# led-group-thin.net
KiCad netlist of a schematic drawn in Altium Designer
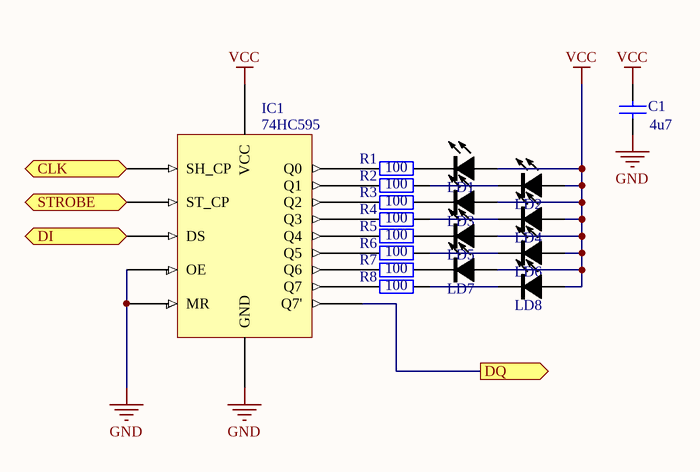
[diagram p0: led-group-thin.SchDoc]

(export (version "E")
  (design (tool "Eeschema 10.0.6"))
  (components
    (comp (ref "C1")
      (value "4u7")
      (footprint "6-0805_M")
      (description "Capacitor")
      (fields (field (name "Comment") "Cap"))
      (libsource (lib "Miscellaneous Devices") (part "Cap"))
    )
    (comp (ref "IC1")
      (value "74HC595")
      (footprint "TSSOP16")
      (description "74HC595 8-bit latched SIPO shift register")
      (libsource (lib "Components") (part "Component_1"))
    )
    (comp (ref "LD1") (value "UV-LED") (footprint "0805-LED") (libsource (lib "Components") (part "UV-LED")))
    (comp (ref "LD2") (value "UV-LED") (footprint "0805-LED") (libsource (lib "Components") (part "UV-LED")))
    (comp (ref "LD3") (value "UV-LED") (footprint "0805-LED") (libsource (lib "Components") (part "UV-LED")))
    (comp (ref "LD4") (value "UV-LED") (footprint "0805-LED") (libsource (lib "Components") (part "UV-LED")))
    (comp (ref "LD5") (value "UV-LED") (footprint "0805-LED") (libsource (lib "Components") (part "UV-LED")))
    (comp (ref "LD6") (value "UV-LED") (footprint "0805-LED") (libsource (lib "Components") (part "UV-LED")))
    (comp (ref "LD7") (value "UV-LED") (footprint "0805-LED") (libsource (lib "Components") (part "UV-LED")))
    (comp (ref "LD8") (value "UV-LED") (footprint "0805-LED") (libsource (lib "Components") (part "UV-LED")))
    (comp (ref "R1")
      (value "100")
      (footprint "6-0805_N")
      (description "Resistor")
      (libsource (lib "Miscellaneous Devices") (part "Res2"))
    )
    (comp (ref "R2")
      (value "100")
      (footprint "6-0805_N")
      (description "Resistor")
      (libsource (lib "Miscellaneous Devices") (part "Res2"))
    )
    (comp (ref "R3")
      (value "100")
      (footprint "6-0805_N")
      (description "Resistor")
      (libsource (lib "Miscellaneous Devices") (part "Res2"))
    )
    (comp (ref "R4")
      (value "100")
      (footprint "6-0805_N")
      (description "Resistor")
      (libsource (lib "Miscellaneous Devices") (part "Res2"))
    )
    (comp (ref "R5")
      (value "100")
      (footprint "6-0805_N")
      (description "Resistor")
      (libsource (lib "Miscellaneous Devices") (part "Res2"))
    )
    (comp (ref "R6")
      (value "100")
      (footprint "6-0805_N")
      (description "Resistor")
      (libsource (lib "Miscellaneous Devices") (part "Res2"))
    )
    (comp (ref "R7")
      (value "100")
      (footprint "6-0805_N")
      (description "Resistor")
      (libsource (lib "Miscellaneous Devices") (part "Res2"))
    )
    (comp (ref "R8")
      (value "100")
      (footprint "6-0805_N")
      (description "Resistor")
      (libsource (lib "Miscellaneous Devices") (part "Res2"))
    )
  )
  (nets
    (net (code "1") (name "/CLK") (class "Default")
      (node (ref "IC1") (pin "11") (pinfunction "SH_CP_11") (pintype "input"))
    )
    (net (code "2") (name "/DI") (class "Default")
      (node (ref "IC1") (pin "14") (pinfunction "DS_14") (pintype "input"))
    )
    (net (code "3") (name "/DQ") (class "Default")
      (node (ref "IC1") (pin "9") (pinfunction "Q7'_9") (pintype "output"))
    )
    (net (code "4") (name "/STROBE") (class "Default")
      (node (ref "IC1") (pin "12") (pinfunction "ST_CP_12") (pintype "input"))
    )
    (net (code "5") (name "GND") (class "Default")
      (node (ref "C1") (pin "1") (pinfunction "1_1") (pintype "passive"))
      (node (ref "IC1") (pin "10") (pinfunction "MR_10") (pintype "input"))
      (node (ref "IC1") (pin "13") (pinfunction "OE_13") (pintype "input"))
      (node (ref "IC1") (pin "8") (pinfunction "GND_8") (pintype "power_in"))
    )
    (net (code "6") (name "Net-(IC1-Q0)") (class "Default")
      (node (ref "IC1") (pin "15") (pinfunction "Q0_15") (pintype "output"))
      (node (ref "R1") (pin "1") (pinfunction "1_1") (pintype "passive"))
    )
    (net (code "7") (name "Net-(IC1-Q1)") (class "Default")
      (node (ref "IC1") (pin "1") (pinfunction "Q1_1") (pintype "output"))
      (node (ref "R2") (pin "1") (pinfunction "1_1") (pintype "passive"))
    )
    (net (code "8") (name "Net-(IC1-Q2)") (class "Default")
      (node (ref "IC1") (pin "2") (pinfunction "Q2_2") (pintype "output"))
      (node (ref "R3") (pin "1") (pinfunction "1_1") (pintype "passive"))
    )
    (net (code "9") (name "Net-(IC1-Q3)") (class "Default")
      (node (ref "IC1") (pin "3") (pinfunction "Q3_3") (pintype "output"))
      (node (ref "R4") (pin "1") (pinfunction "1_1") (pintype "passive"))
    )
    (net (code "10") (name "Net-(IC1-Q4)") (class "Default")
      (node (ref "IC1") (pin "4") (pinfunction "Q4_4") (pintype "output"))
      (node (ref "R5") (pin "1") (pinfunction "1_1") (pintype "passive"))
    )
    (net (code "11") (name "Net-(IC1-Q5)") (class "Default")
      (node (ref "IC1") (pin "5") (pinfunction "Q5_5") (pintype "output"))
      (node (ref "R6") (pin "1") (pinfunction "1_1") (pintype "passive"))
    )
    (net (code "12") (name "Net-(IC1-Q6)") (class "Default")
      (node (ref "IC1") (pin "6") (pinfunction "Q6_6") (pintype "output"))
      (node (ref "R7") (pin "1") (pinfunction "1_1") (pintype "passive"))
    )
    (net (code "13") (name "Net-(IC1-Q7)") (class "Default")
      (node (ref "IC1") (pin "7") (pinfunction "Q7_7") (pintype "output"))
      (node (ref "R8") (pin "1") (pinfunction "1_1") (pintype "passive"))
    )
    (net (code "14") (name "Net-(LD1-PadK)") (class "Default")
      (node (ref "LD1") (pin "K") (pinfunction "K_K") (pintype "passive"))
      (node (ref "R1") (pin "2") (pinfunction "2_2") (pintype "passive"))
    )
    (net (code "15") (name "Net-(LD2-PadK)") (class "Default")
      (node (ref "LD2") (pin "K") (pinfunction "K_K") (pintype "passive"))
      (node (ref "R2") (pin "2") (pinfunction "2_2") (pintype "passive"))
    )
    (net (code "16") (name "Net-(LD3-PadK)") (class "Default")
      (node (ref "LD3") (pin "K") (pinfunction "K_K") (pintype "passive"))
      (node (ref "R3") (pin "2") (pinfunction "2_2") (pintype "passive"))
    )
    (net (code "17") (name "Net-(LD4-PadK)") (class "Default")
      (node (ref "LD4") (pin "K") (pinfunction "K_K") (pintype "passive"))
      (node (ref "R4") (pin "2") (pinfunction "2_2") (pintype "passive"))
    )
    (net (code "18") (name "Net-(LD5-PadK)") (class "Default")
      (node (ref "LD5") (pin "K") (pinfunction "K_K") (pintype "passive"))
      (node (ref "R5") (pin "2") (pinfunction "2_2") (pintype "passive"))
    )
    (net (code "19") (name "Net-(LD6-PadK)") (class "Default")
      (node (ref "LD6") (pin "K") (pinfunction "K_K") (pintype "passive"))
      (node (ref "R6") (pin "2") (pinfunction "2_2") (pintype "passive"))
    )
    (net (code "20") (name "Net-(LD7-PadK)") (class "Default")
      (node (ref "LD7") (pin "K") (pinfunction "K_K") (pintype "passive"))
      (node (ref "R7") (pin "2") (pinfunction "2_2") (pintype "passive"))
    )
    (net (code "21") (name "Net-(LD8-PadK)") (class "Default")
      (node (ref "LD8") (pin "K") (pinfunction "K_K") (pintype "passive"))
      (node (ref "R8") (pin "2") (pinfunction "2_2") (pintype "passive"))
    )
    (net (code "22") (name "VCC") (class "Default")
      (node (ref "C1") (pin "2") (pinfunction "2_2") (pintype "passive"))
      (node (ref "IC1") (pin "16") (pinfunction "VCC_16") (pintype "power_in"))
      (node (ref "LD1") (pin "A") (pinfunction "A_A") (pintype "passive"))
      (node (ref "LD2") (pin "A") (pinfunction "A_A") (pintype "passive"))
      (node (ref "LD3") (pin "A") (pinfunction "A_A") (pintype "passive"))
      (node (ref "LD4") (pin "A") (pinfunction "A_A") (pintype "passive"))
      (node (ref "LD5") (pin "A") (pinfunction "A_A") (pintype "passive"))
      (node (ref "LD6") (pin "A") (pinfunction "A_A") (pintype "passive"))
      (node (ref "LD7") (pin "A") (pinfunction "A_A") (pintype "passive"))
      (node (ref "LD8") (pin "A") (pinfunction "A_A") (pintype "passive"))
    )
  )
)
